# ITALY_DOZATOR_el.net
KiCad netlist of a schematic drawn in EAGLE
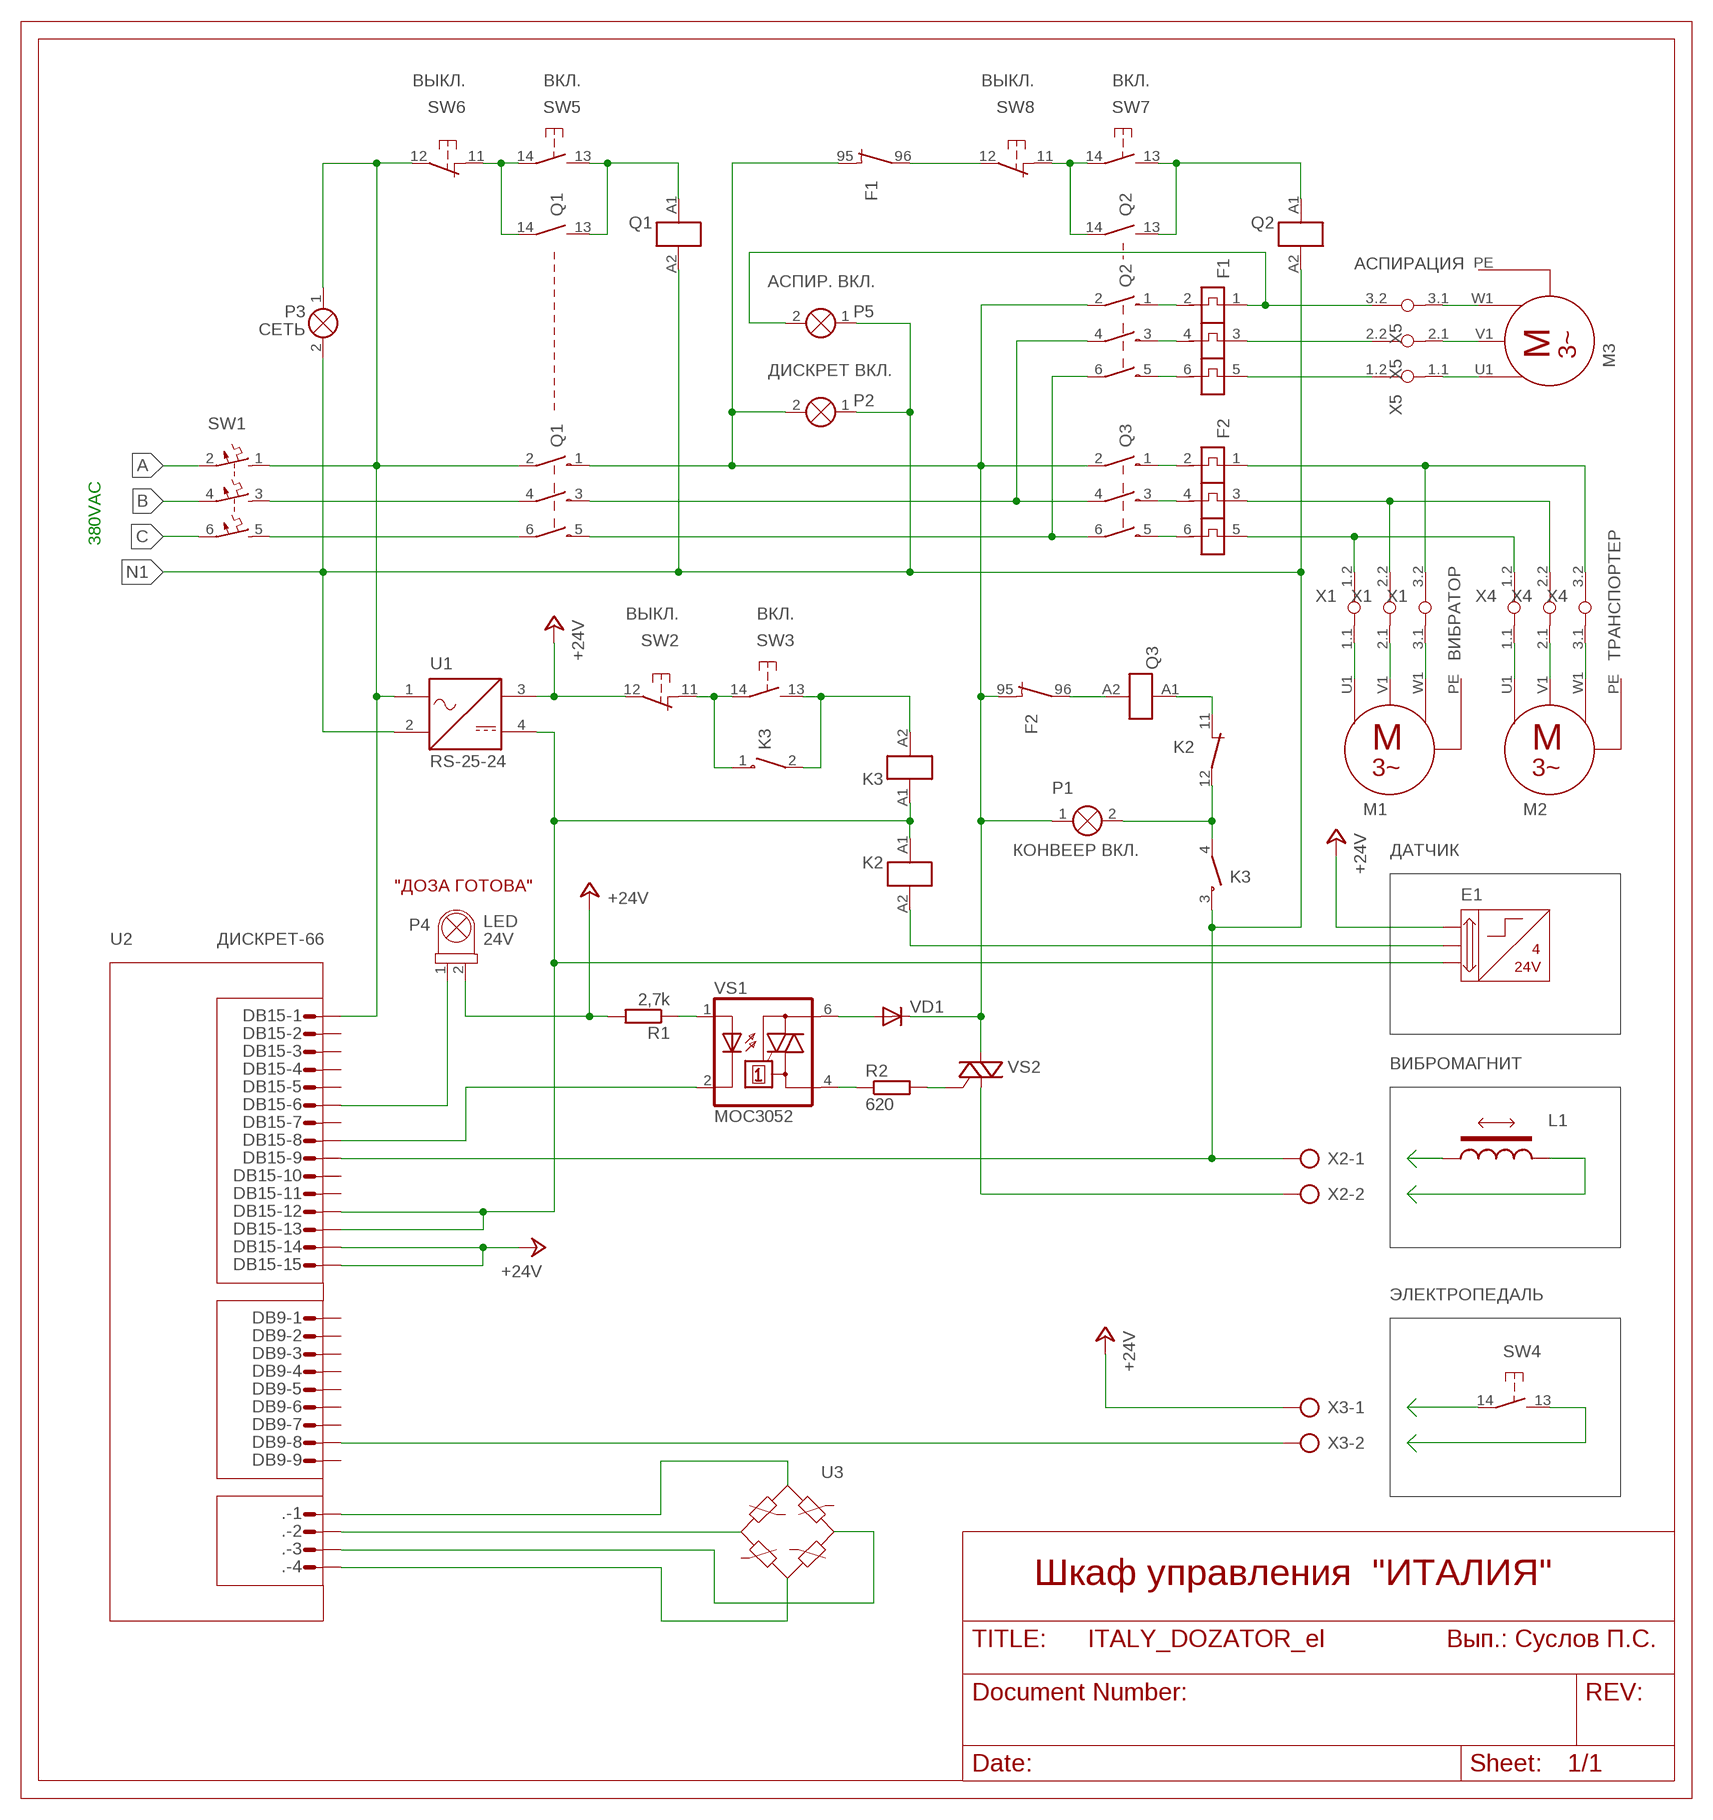
[diagram p0: schematic, sheet 1]

(export (version "E")
  (design (tool "Eeschema 10.0.6"))
  (components
    (comp (ref ".")
      (value "L04P")
      (footprint "eagle-import:L04P")
      (libsource (lib "eagle-import") (part "L04P"))
    )
    (comp (ref "DB9")
      (value "L09P")
      (footprint "eagle-import:L09P")
      (libsource (lib "eagle-import") (part "L09P"))
    )
    (comp (ref "DB15")
      (value "L15P")
      (footprint "eagle-import:L15P")
      (libsource (lib "eagle-import") (part "L15P"))
    )
    (comp (ref "E1")
      (value "6158EB")
      (footprint "eagle-import:6158EB")
      (libsource (lib "eagle-import") (part "6158EB"))
    )
    (comp (ref "F1")
      (value "MOTORSCHUTZSCHALTER_3-POL_THERM_AUSLOESUNG_HILFSKONTAKTE")
      (footprint "eagle-import:MOTORSCHUTZSCHALTER_3-POL_THERM_AUSLOESUNG_HILFSKONTAKT_95_96_97_98")
      (libsource (lib "eagle-import") (part "MOTORSCHUTZSCHALTER_3-POL_THERM_AUSLOESUNG_HILFSKONTAKTE"))
    )
    (comp (ref "F2")
      (value "MOTORSCHUTZSCHALTER_3-POL_THERM_AUSLOESUNG_HILFSKONTAKTE")
      (footprint "eagle-import:MOTORSCHUTZSCHALTER_3-POL_THERM_AUSLOESUNG_HILFSKONTAKT_95_96_97_98")
      (libsource (lib "eagle-import") (part "MOTORSCHUTZSCHALTER_3-POL_THERM_AUSLOESUNG_HILFSKONTAKTE"))
    )
    (comp (ref "K2")
      (value "HILFSSCHUETZ_11-12")
      (footprint "eagle-import:HILFSSCHUETZ_11-12")
      (libsource (lib "eagle-import") (part "HILFSSCHUETZ_11-12"))
    )
    (comp (ref "K3")
      (value "HAUPTSCHUETZ_2-POL")
      (footprint "eagle-import:HAUPTSCHUETZ_2-POL")
      (libsource (lib "eagle-import") (part "HAUPTSCHUETZ_2-POL"))
    )
    (comp (ref "L1")
      (value "L-US0204/5")
      (footprint "eagle-import:0204_5")
      (libsource (lib "eagle-import") (part "L-US0204/5"))
    )
    (comp (ref "M1")
      (value "MOTOR_3-POL_PE")
      (footprint "eagle-import:MOTOR_3-POL_PE")
      (libsource (lib "eagle-import") (part "MOTOR_3-POL_PE"))
    )
    (comp (ref "M2")
      (value "MOTOR_3-POL_PE")
      (footprint "eagle-import:MOTOR_3-POL_PE")
      (libsource (lib "eagle-import") (part "MOTOR_3-POL_PE"))
    )
    (comp (ref "M3")
      (value "MOTOR_3-POL_PE")
      (footprint "eagle-import:MOTOR_3-POL_PE")
      (libsource (lib "eagle-import") (part "MOTOR_3-POL_PE"))
    )
    (comp (ref "P1")
      (value "КОНВЕЕР ВКЛ.")
      (footprint "eagle-import:LAMPE")
      (libsource (lib "eagle-import") (part "SIGNALLAMPE"))
    )
    (comp (ref "P2")
      (value "ДИСКРЕТ ВКЛ.")
      (footprint "eagle-import:LAMPE")
      (libsource (lib "eagle-import") (part "SIGNALLAMPE"))
    )
    (comp (ref "P3")
      (value "СЕТЬ")
      (footprint "eagle-import:LAMPE")
      (libsource (lib "eagle-import") (part "SIGNALLAMPE"))
    )
    (comp (ref "P4")
      (value "BLINK/BLITZLEUCHTE")
      (footprint "eagle-import:LAMPE")
      (libsource (lib "eagle-import") (part "BLINK/BLITZLEUCHTE"))
    )
    (comp (ref "P5")
      (value "АСПИР. ВКЛ.")
      (footprint "eagle-import:LAMPE")
      (libsource (lib "eagle-import") (part "SIGNALLAMPE"))
    )
    (comp (ref "Q1")
      (value "HAUPTSCHUETZ_3-POL_HILFSKONTAKT_13-14")
      (footprint "eagle-import:HAUPTSCHUETZ_3-POL+HILFSKONTAKT_13-14")
      (libsource (lib "eagle-import") (part "HAUPTSCHUETZ_3-POL_HILFSKONTAKT_13-14"))
    )
    (comp (ref "Q2")
      (value "HAUPTSCHUETZ_3-POL_HILFSKONTAKT_13-14")
      (footprint "eagle-import:HAUPTSCHUETZ_3-POL+HILFSKONTAKT_13-14")
      (libsource (lib "eagle-import") (part "HAUPTSCHUETZ_3-POL_HILFSKONTAKT_13-14"))
    )
    (comp (ref "Q3")
      (value "HAUPTSCHUETZ_3-POL")
      (footprint "eagle-import:HAUPTSCHUETZ_3-POL")
      (libsource (lib "eagle-import") (part "HAUPTSCHUETZ_3-POL"))
    )
    (comp (ref "R1")
      (value "2,7k")
      (footprint "eagle-import:0204V")
      (libsource (lib "eagle-import") (part "R-EU_0204/2V"))
    )
    (comp (ref "R2")
      (value "620")
      (footprint "eagle-import:0204V")
      (libsource (lib "eagle-import") (part "R-EU_0204/2V"))
    )
    (comp (ref "SW1")
      (value "LEITUNGSSCHUTZSCHALTER_3-POL")
      (footprint "eagle-import:LEITUNGSSCHUTZSCHALTER_3-POL")
      (libsource (lib "eagle-import") (part "LEITUNGSSCHUTZSCHALTER_3-POL"))
    )
    (comp (ref "SW2")
      (value "ВЫКЛ.")
      (footprint "eagle-import:OEFFNER_TASTSCHALTER")
      (libsource (lib "eagle-import") (part "OEFFNER_TASTSCHALTER"))
    )
    (comp (ref "SW3")
      (value "ВКЛ.")
      (footprint "eagle-import:SCHLIESSER_TASTSCHALTER")
      (libsource (lib "eagle-import") (part "SCHLIESSER_TASTSCHALTER"))
    )
    (comp (ref "SW4")
      (value "SCHLIESSER_TASTSCHALTER")
      (footprint "eagle-import:SCHLIESSER_TASTSCHALTER")
      (libsource (lib "eagle-import") (part "SCHLIESSER_TASTSCHALTER"))
    )
    (comp (ref "SW5")
      (value "ВКЛ.")
      (footprint "eagle-import:SCHLIESSER_TASTSCHALTER")
      (libsource (lib "eagle-import") (part "SCHLIESSER_TASTSCHALTER"))
    )
    (comp (ref "SW6")
      (value "ВЫКЛ.")
      (footprint "eagle-import:OEFFNER_TASTSCHALTER")
      (libsource (lib "eagle-import") (part "OEFFNER_TASTSCHALTER"))
    )
    (comp (ref "SW7")
      (value "ВКЛ.")
      (footprint "eagle-import:SCHLIESSER_TASTSCHALTER")
      (libsource (lib "eagle-import") (part "SCHLIESSER_TASTSCHALTER"))
    )
    (comp (ref "SW8")
      (value "ВЫКЛ.")
      (footprint "eagle-import:OEFFNER_TASTSCHALTER")
      (libsource (lib "eagle-import") (part "OEFFNER_TASTSCHALTER"))
    )
    (comp (ref "U1")
      (value "RS-25-24")
      (footprint "eagle-import:NETZTEIL_GLEICHSPANNUNG")
      (libsource (lib "eagle-import") (part "NETZTEIL_GLEICHSPANNUNG"))
    )
    (comp (ref "VD1")
      (value "1N4148DO35-7")
      (footprint "eagle-import:DO35-7")
      (libsource (lib "eagle-import") (part "1N4148DO35-7"))
    )
    (comp (ref "VS1")
      (value "MOC3052")
      (footprint "eagle-import:DIL06B")
      (libsource (lib "eagle-import") (part "MOC30T42"))
    )
    (comp (ref "VS2")
      (value "TRIAC")
      (footprint "eagle-import:TRIAC")
      (libsource (lib "eagle-import") (part "TRIAC"))
    )
    (comp (ref "X1")
      (value "KLEMME_1-3")
      (footprint "eagle-import:KLEMME_1-3")
      (libsource (lib "eagle-import") (part "KLEMME_1-3"))
    )
    (comp (ref "X2")
      (value "AK500/2")
      (footprint "eagle-import:AK500_2")
      (libsource (lib "eagle-import") (part "AK500/2"))
    )
    (comp (ref "X3")
      (value "AK500/2")
      (footprint "eagle-import:AK500_2")
      (libsource (lib "eagle-import") (part "AK500/2"))
    )
    (comp (ref "X4")
      (value "KLEMME_1-3")
      (footprint "eagle-import:KLEMME_1-3")
      (libsource (lib "eagle-import") (part "KLEMME_1-3"))
    )
    (comp (ref "X5")
      (value "KLEMME_1-3")
      (footprint "eagle-import:KLEMME_1-3")
      (libsource (lib "eagle-import") (part "KLEMME_1-3"))
    )
  )
  (nets
    (net (code "1") (name "+24V") (class "Default")
      (node (ref "DB15") (pin "14") (pinfunction "S_14") (pintype "passive"))
      (node (ref "DB15") (pin "15") (pinfunction "S_15") (pintype "passive"))
      (node (ref "P4") (pin "2") (pinfunction "X2_2") (pintype "passive"))
      (node (ref "R1") (pin "2") (pinfunction "2_2") (pintype "passive"))
      (node (ref "SW2") (pin "12") (pinfunction "2_12") (pintype "input"))
      (node (ref "U1") (pin "3") (pinfunction "3_3") (pintype "passive"))
      (node (ref "X3") (pin "1") (pinfunction "KL_1") (pintype "passive"))
    )
    (net (code "2") (name "A") (class "Default")
      (node (ref "SW1") (pin "2") (pinfunction "2_2") (pintype "passive"))
    )
    (net (code "3") (name "B") (class "Default")
      (node (ref "SW1") (pin "4") (pinfunction "4_4") (pintype "passive"))
    )
    (net (code "4") (name "C") (class "Default")
      (node (ref "SW1") (pin "6") (pinfunction "6_6") (pintype "passive"))
    )
    (net (code "5") (name "N1") (class "Default")
      (node (ref "DB15") (pin "9") (pinfunction "S_9") (pintype "passive"))
      (node (ref "K3") (pin "3") (pinfunction "3_3") (pintype "passive"))
      (node (ref "P2") (pin "1") (pinfunction "X1_1") (pintype "passive"))
      (node (ref "P3") (pin "2") (pinfunction "X2_2") (pintype "passive"))
      (node (ref "P5") (pin "1") (pinfunction "X1_1") (pintype "passive"))
      (node (ref "Q1") (pin "A2") (pinfunction "A2_A2") (pintype "input"))
      (node (ref "Q2") (pin "A2") (pinfunction "A2_A2") (pintype "input"))
      (node (ref "U1") (pin "2") (pinfunction "2_2") (pintype "passive"))
      (node (ref "X2") (pin "1") (pinfunction "KL_1") (pintype "passive"))
    )
    (net (code "6") (name "Net-(DB9H-S)") (class "Default")
      (node (ref "DB9") (pin "8") (pinfunction "S_8") (pintype "passive"))
      (node (ref "X3") (pin "2") (pinfunction "KL_2") (pintype "passive"))
    )
    (net (code "7") (name "Net-(DB15A-S)") (class "Default")
      (node (ref "DB15") (pin "1") (pinfunction "S_1") (pintype "passive"))
      (node (ref "P3") (pin "1") (pinfunction "X1_1") (pintype "passive"))
      (node (ref "Q1") (pin "2") (pinfunction "2_2") (pintype "passive"))
      (node (ref "SW1") (pin "1") (pinfunction "1_1") (pintype "passive"))
      (node (ref "SW6") (pin "12") (pinfunction "2_12") (pintype "input"))
      (node (ref "U1") (pin "1") (pinfunction "1_1") (pintype "passive"))
    )
    (net (code "8") (name "Net-(DB15D-S)") (class "Default")
      (node (ref "DB15") (pin "12") (pinfunction "S_12") (pintype "passive"))
      (node (ref "DB15") (pin "13") (pinfunction "S_13") (pintype "passive"))
      (node (ref "K2") (pin "A1") (pinfunction "A1_A1") (pintype "input"))
      (node (ref "K3") (pin "A1") (pinfunction "A1_A1") (pintype "input"))
      (node (ref "U1") (pin "4") (pinfunction "4_4") (pintype "passive"))
    )
    (net (code "9") (name "Net-(DB15L-S)") (class "Default")
      (node (ref "DB15") (pin "6") (pinfunction "S_6") (pintype "passive"))
      (node (ref "P4") (pin "1") (pinfunction "X1_1") (pintype "passive"))
    )
    (net (code "10") (name "Net-(DB15N-S)") (class "Default")
      (node (ref "DB15") (pin "8") (pinfunction "S_8") (pintype "passive"))
      (node (ref "VS1") (pin "2") (pinfunction "C_2") (pintype "passive"))
    )
    (net (code "11") (name "Net-(E1-Pad1)") (class "Default")
      (node (ref "E1") (pin "1") (pinfunction "1_1") (pintype "passive"))
      (node (ref "K2") (pin "A2") (pinfunction "A2_A2") (pintype "input"))
    )
    (net (code "12") (name "Net-(F1-Pad2)") (class "Default")
      (node (ref "F1") (pin "2") (pinfunction "2_2") (pintype "passive"))
      (node (ref "Q2") (pin "1") (pinfunction "1_1") (pintype "passive"))
    )
    (net (code "13") (name "Net-(F1-Pad3)") (class "Default")
      (node (ref "F1") (pin "3") (pinfunction "3_3") (pintype "passive"))
      (node (ref "X5") (pin "2.2") (pinfunction "2.2_2.2") (pintype "passive"))
    )
    (net (code "14") (name "Net-(F1-Pad4)") (class "Default")
      (node (ref "F1") (pin "4") (pinfunction "4_4") (pintype "passive"))
      (node (ref "Q2") (pin "3") (pinfunction "3_3") (pintype "passive"))
    )
    (net (code "15") (name "Net-(F1-Pad5)") (class "Default")
      (node (ref "F1") (pin "5") (pinfunction "5_5") (pintype "passive"))
      (node (ref "X5") (pin "1.2") (pinfunction "1.2_1.2") (pintype "passive"))
    )
    (net (code "16") (name "Net-(F1-Pad6)") (class "Default")
      (node (ref "F1") (pin "6") (pinfunction "6_6") (pintype "passive"))
      (node (ref "Q2") (pin "5") (pinfunction "5_5") (pintype "passive"))
    )
    (net (code "17") (name "Net-(F2-Pad1)") (class "Default")
      (node (ref "F2") (pin "1") (pinfunction "1_1") (pintype "passive"))
      (node (ref "X1") (pin "3.2") (pinfunction "3.2_3.2") (pintype "passive"))
      (node (ref "X4") (pin "3.2") (pinfunction "3.2_3.2") (pintype "passive"))
    )
    (net (code "18") (name "Net-(F2-Pad2)") (class "Default")
      (node (ref "F2") (pin "2") (pinfunction "2_2") (pintype "passive"))
      (node (ref "Q3") (pin "1") (pinfunction "1_1") (pintype "passive"))
    )
    (net (code "19") (name "Net-(F2-Pad3)") (class "Default")
      (node (ref "F2") (pin "3") (pinfunction "3_3") (pintype "passive"))
      (node (ref "X1") (pin "2.2") (pinfunction "2.2_2.2") (pintype "passive"))
      (node (ref "X4") (pin "2.2") (pinfunction "2.2_2.2") (pintype "passive"))
    )
    (net (code "20") (name "Net-(F2-Pad4)") (class "Default")
      (node (ref "F2") (pin "4") (pinfunction "4_4") (pintype "passive"))
      (node (ref "Q3") (pin "3") (pinfunction "3_3") (pintype "passive"))
    )
    (net (code "21") (name "Net-(F2-Pad5)") (class "Default")
      (node (ref "F2") (pin "5") (pinfunction "5_5") (pintype "passive"))
      (node (ref "X1") (pin "1.2") (pinfunction "1.2_1.2") (pintype "passive"))
      (node (ref "X4") (pin "1.2") (pinfunction "1.2_1.2") (pintype "passive"))
    )
    (net (code "22") (name "Net-(F2-Pad6)") (class "Default")
      (node (ref "F2") (pin "6") (pinfunction "6_6") (pintype "passive"))
      (node (ref "Q3") (pin "5") (pinfunction "5_5") (pintype "passive"))
    )
    (net (code "23") (name "Net-(F2-Pad96)") (class "Default")
      (node (ref "F2") (pin "96") (pinfunction "96_96") (pintype "passive"))
      (node (ref "Q3") (pin "A2") (pinfunction "A2_A2") (pintype "input"))
    )
    (net (code "24") (name "Net-(K2A-1)") (class "Default")
      (node (ref "K2") (pin "11") (pinfunction "1_11") (pintype "passive"))
      (node (ref "Q3") (pin "A1") (pinfunction "A1_A1") (pintype "input"))
    )
    (net (code "25") (name "Net-(K2A-2)") (class "Default")
      (node (ref "K2") (pin "12") (pinfunction "2_12") (pintype "passive"))
      (node (ref "K3") (pin "4") (pinfunction "4_4") (pintype "passive"))
      (node (ref "P1") (pin "2") (pinfunction "X2_2") (pintype "passive"))
    )
    (net (code "26") (name "Net-(K3B-3)") (class "Default")
      (node (ref "K3") (pin "1") (pinfunction "3_1") (pintype "passive"))
      (node (ref "SW2") (pin "11") (pinfunction "1_11") (pintype "input"))
      (node (ref "SW3") (pin "14") (pinfunction "4_14") (pintype "input"))
    )
    (net (code "27") (name "Net-(K3B-4)") (class "Default")
      (node (ref "K3") (pin "2") (pinfunction "4_2") (pintype "passive"))
      (node (ref "K3") (pin "A2") (pinfunction "A2_A2") (pintype "input"))
      (node (ref "SW3") (pin "13") (pinfunction "3_13") (pintype "input"))
    )
    (net (code "28") (name "Net-(M1-PadU1)") (class "Default")
      (node (ref "M1") (pin "U1") (pinfunction "U1_U1") (pintype "passive"))
      (node (ref "X1") (pin "1.1") (pinfunction "1.1_1.1") (pintype "passive"))
    )
    (net (code "29") (name "Net-(M1-PadV1)") (class "Default")
      (node (ref "M1") (pin "V1") (pinfunction "V1_V1") (pintype "passive"))
      (node (ref "X1") (pin "2.1") (pinfunction "2.1_2.1") (pintype "passive"))
    )
    (net (code "30") (name "Net-(M1-PadW1)") (class "Default")
      (node (ref "M1") (pin "W1") (pinfunction "W1_W1") (pintype "passive"))
      (node (ref "X1") (pin "3.1") (pinfunction "3.1_3.1") (pintype "passive"))
    )
    (net (code "31") (name "Net-(M2-PadU1)") (class "Default")
      (node (ref "M2") (pin "U1") (pinfunction "U1_U1") (pintype "passive"))
      (node (ref "X4") (pin "1.1") (pinfunction "1.1_1.1") (pintype "passive"))
    )
    (net (code "32") (name "Net-(M2-PadV1)") (class "Default")
      (node (ref "M2") (pin "V1") (pinfunction "V1_V1") (pintype "passive"))
      (node (ref "X4") (pin "2.1") (pinfunction "2.1_2.1") (pintype "passive"))
    )
    (net (code "33") (name "Net-(M2-PadW1)") (class "Default")
      (node (ref "M2") (pin "W1") (pinfunction "W1_W1") (pintype "passive"))
      (node (ref "X4") (pin "3.1") (pinfunction "3.1_3.1") (pintype "passive"))
    )
    (net (code "34") (name "Net-(M3-PadU1)") (class "Default")
      (node (ref "M3") (pin "U1") (pinfunction "U1_U1") (pintype "passive"))
      (node (ref "X5") (pin "1.1") (pinfunction "1.1_1.1") (pintype "passive"))
    )
    (net (code "35") (name "Net-(M3-PadV1)") (class "Default")
      (node (ref "M3") (pin "V1") (pinfunction "V1_V1") (pintype "passive"))
      (node (ref "X5") (pin "2.1") (pinfunction "2.1_2.1") (pintype "passive"))
    )
    (net (code "36") (name "Net-(M3-PadW1)") (class "Default")
      (node (ref "M3") (pin "W1") (pinfunction "W1_W1") (pintype "passive"))
      (node (ref "X5") (pin "3.1") (pinfunction "3.1_3.1") (pintype "passive"))
    )
    (net (code "37") (name "Net-(P1-X1)") (class "Default")
      (node (ref "F1") (pin "95") (pinfunction "95_95") (pintype "passive"))
      (node (ref "F2") (pin "95") (pinfunction "95_95") (pintype "passive"))
      (node (ref "P1") (pin "1") (pinfunction "X1_1") (pintype "passive"))
      (node (ref "P2") (pin "2") (pinfunction "X2_2") (pintype "passive"))
      (node (ref "Q1") (pin "1") (pinfunction "1_1") (pintype "passive"))
      (node (ref "Q2") (pin "2") (pinfunction "2_2") (pintype "passive"))
      (node (ref "Q3") (pin "2") (pinfunction "2_2") (pintype "passive"))
      (node (ref "VD1") (pin "C") (pinfunction "C_C") (pintype "passive"))
      (node (ref "VS2") (pin "A1") (pinfunction "A1_A1") (pintype "passive"))
    )
    (net (code "38") (name "Net-(P5-X2)") (class "Default")
      (node (ref "F1") (pin "1") (pinfunction "1_1") (pintype "passive"))
      (node (ref "P5") (pin "2") (pinfunction "X2_2") (pintype "passive"))
      (node (ref "X5") (pin "3.2") (pinfunction "3.2_3.2") (pintype "passive"))
    )
    (net (code "39") (name "Net-(Q1-Pad3)") (class "Default")
      (node (ref "Q1") (pin "3") (pinfunction "3_3") (pintype "passive"))
      (node (ref "Q2") (pin "4") (pinfunction "4_4") (pintype "passive"))
      (node (ref "Q3") (pin "4") (pinfunction "4_4") (pintype "passive"))
    )
    (net (code "40") (name "Net-(Q1-Pad4)") (class "Default")
      (node (ref "Q1") (pin "4") (pinfunction "4_4") (pintype "passive"))
      (node (ref "SW1") (pin "3") (pinfunction "3_3") (pintype "passive"))
    )
    (net (code "41") (name "Net-(Q1-Pad5)") (class "Default")
      (node (ref "Q1") (pin "5") (pinfunction "5_5") (pintype "passive"))
      (node (ref "Q2") (pin "6") (pinfunction "6_6") (pintype "passive"))
      (node (ref "Q3") (pin "6") (pinfunction "6_6") (pintype "passive"))
    )
    (net (code "42") (name "Net-(Q1-Pad6)") (class "Default")
      (node (ref "Q1") (pin "6") (pinfunction "6_6") (pintype "passive"))
      (node (ref "SW1") (pin "5") (pinfunction "5_5") (pintype "passive"))
    )
    (net (code "43") (name "Net-(Q1B-3)") (class "Default")
      (node (ref "Q1") (pin "13") (pinfunction "3_13") (pintype "passive"))
      (node (ref "Q1") (pin "A1") (pinfunction "A1_A1") (pintype "input"))
      (node (ref "SW5") (pin "13") (pinfunction "3_13") (pintype "input"))
    )
    (net (code "44") (name "Net-(Q1B-4)") (class "Default")
      (node (ref "Q1") (pin "14") (pinfunction "4_14") (pintype "passive"))
      (node (ref "SW5") (pin "14") (pinfunction "4_14") (pintype "input"))
      (node (ref "SW6") (pin "11") (pinfunction "1_11") (pintype "input"))
    )
    (net (code "45") (name "Net-(Q2B-3)") (class "Default")
      (node (ref "Q2") (pin "13") (pinfunction "3_13") (pintype "passive"))
      (node (ref "Q2") (pin "A1") (pinfunction "A1_A1") (pintype "input"))
      (node (ref "SW7") (pin "13") (pinfunction "3_13") (pintype "input"))
    )
    (net (code "46") (name "Net-(Q2B-4)") (class "Default")
      (node (ref "Q2") (pin "14") (pinfunction "4_14") (pintype "passive"))
      (node (ref "SW7") (pin "14") (pinfunction "4_14") (pintype "input"))
      (node (ref "SW8") (pin "11") (pinfunction "1_11") (pintype "input"))
    )
    (net (code "47") (name "Net-(R2-Pad2)") (class "Default")
      (node (ref "R2") (pin "2") (pinfunction "2_2") (pintype "passive"))
      (node (ref "VS2") (pin "G") (pinfunction "G_G") (pintype "passive"))
    )
    (net (code "48") (name "Net-(SW8-2)") (class "Default")
      (node (ref "F1") (pin "96") (pinfunction "96_96") (pintype "passive"))
      (node (ref "SW8") (pin "12") (pinfunction "2_12") (pintype "input"))
    )
    (net (code "49") (name "Net-(VS1-A)") (class "Default")
      (node (ref "R1") (pin "1") (pinfunction "1_1") (pintype "passive"))
      (node (ref "VS1") (pin "1") (pinfunction "A_1") (pintype "passive"))
    )
    (net (code "50") (name "Net-(VS1-A1)") (class "Default")
      (node (ref "R2") (pin "1") (pinfunction "1_1") (pintype "passive"))
      (node (ref "VS1") (pin "4") (pinfunction "A1_4") (pintype "passive"))
    )
    (net (code "51") (name "Net-(VS1-A2)") (class "Default")
      (node (ref "VD1") (pin "A") (pinfunction "A_A") (pintype "passive"))
      (node (ref "VS1") (pin "6") (pinfunction "A2_6") (pintype "passive"))
    )
    (net (code "52") (name "Net-(X2B-KL)") (class "Default")
      (node (ref "VS2") (pin "A2") (pinfunction "A2_A2") (pintype "passive"))
      (node (ref "X2") (pin "2") (pinfunction "KL_2") (pintype "passive"))
    )
    (net (code "53") (name "unconnected-(.A-S-Pad1)") (class "Default")
      (node (ref ".") (pin "1") (pinfunction "S_1") (pintype "passive"))
    )
    (net (code "54") (name "unconnected-(.B-S-Pad2)") (class "Default")
      (node (ref ".") (pin "2") (pinfunction "S_2") (pintype "passive"))
    )
    (net (code "55") (name "unconnected-(.C-S-Pad3)") (class "Default")
      (node (ref ".") (pin "3") (pinfunction "S_3") (pintype "passive"))
    )
    (net (code "56") (name "unconnected-(.D-S-Pad4)") (class "Default")
      (node (ref ".") (pin "4") (pinfunction "S_4") (pintype "passive"))
    )
    (net (code "57") (name "unconnected-(DB9A-S-Pad1)") (class "Default")
      (node (ref "DB9") (pin "1") (pinfunction "S_1") (pintype "passive"))
    )
    (net (code "58") (name "unconnected-(DB9B-S-Pad2)") (class "Default")
      (node (ref "DB9") (pin "2") (pinfunction "S_2") (pintype "passive"))
    )
    (net (code "59") (name "unconnected-(DB9C-S-Pad3)") (class "Default")
      (node (ref "DB9") (pin "3") (pinfunction "S_3") (pintype "passive"))
    )
    (net (code "60") (name "unconnected-(DB9D-S-Pad4)") (class "Default")
      (node (ref "DB9") (pin "4") (pinfunction "S_4") (pintype "passive"))
    )
    (net (code "61") (name "unconnected-(DB9E-S-Pad5)") (class "Default")
      (node (ref "DB9") (pin "5") (pinfunction "S_5") (pintype "passive"))
    )
    (net (code "62") (name "unconnected-(DB9F-S-Pad6)") (class "Default")
      (node (ref "DB9") (pin "6") (pinfunction "S_6") (pintype "passive"))
    )
    (net (code "63") (name "unconnected-(DB9G-S-Pad7)") (class "Default")
      (node (ref "DB9") (pin "7") (pinfunction "S_7") (pintype "passive"))
    )
    (net (code "64") (name "unconnected-(DB9I-S-Pad9)") (class "Default")
      (node (ref "DB9") (pin "9") (pinfunction "S_9") (pintype "passive"))
    )
    (net (code "65") (name "unconnected-(DB15B-S-Pad10)") (class "Default")
      (node (ref "DB15") (pin "10") (pinfunction "S_10") (pintype "passive"))
    )
    (net (code "66") (name "unconnected-(DB15C-S-Pad11)") (class "Default")
      (node (ref "DB15") (pin "11") (pinfunction "S_11") (pintype "passive"))
    )
    (net (code "67") (name "unconnected-(DB15H-S-Pad2)") (class "Default")
      (node (ref "DB15") (pin "2") (pinfunction "S_2") (pintype "passive"))
    )
    (net (code "68") (name "unconnected-(DB15I-S-Pad3)") (class "Default")
      (node (ref "DB15") (pin "3") (pinfunction "S_3") (pintype "passive"))
    )
    (net (code "69") (name "unconnected-(DB15J-S-Pad4)") (class "Default")
      (node (ref "DB15") (pin "4") (pinfunction "S_4") (pintype "passive"))
    )
    (net (code "70") (name "unconnected-(DB15K-S-Pad5)") (class "Default")
      (node (ref "DB15") (pin "5") (pinfunction "S_5") (pintype "passive"))
    )
    (net (code "71") (name "unconnected-(DB15M-S-Pad7)") (class "Default")
      (node (ref "DB15") (pin "7") (pinfunction "S_7") (pintype "passive"))
    )
    (net (code "72") (name "unconnected-(L1-Pad1)") (class "Default")
      (node (ref "L1") (pin "1") (pinfunction "1_1") (pintype "passive"))
    )
    (net (code "73") (name "unconnected-(L1-Pad2)") (class "Default")
      (node (ref "L1") (pin "2") (pinfunction "2_2") (pintype "passive"))
    )
    (net (code "74") (name "unconnected-(M1-PadPE)") (class "Default")
      (node (ref "M1") (pin "PE") (pinfunction "PE_PE") (pintype "passive"))
    )
    (net (code "75") (name "unconnected-(M2-PadPE)") (class "Default")
      (node (ref "M2") (pin "PE") (pinfunction "PE_PE") (pintype "passive"))
    )
    (net (code "76") (name "unconnected-(M3-PadPE)") (class "Default")
      (node (ref "M3") (pin "PE") (pinfunction "PE_PE") (pintype "passive"))
    )
    (net (code "77") (name "unconnected-(SW4-3-Pad13)") (class "Default")
      (node (ref "SW4") (pin "13") (pinfunction "3_13") (pintype "input"))
    )
    (net (code "78") (name "unconnected-(SW4-4-Pad14)") (class "Default")
      (node (ref "SW4") (pin "14") (pinfunction "4_14") (pintype "input"))
    )
  )
)
